# Connectors.net
KiCad netlist of a schematic drawn in Altium Designer
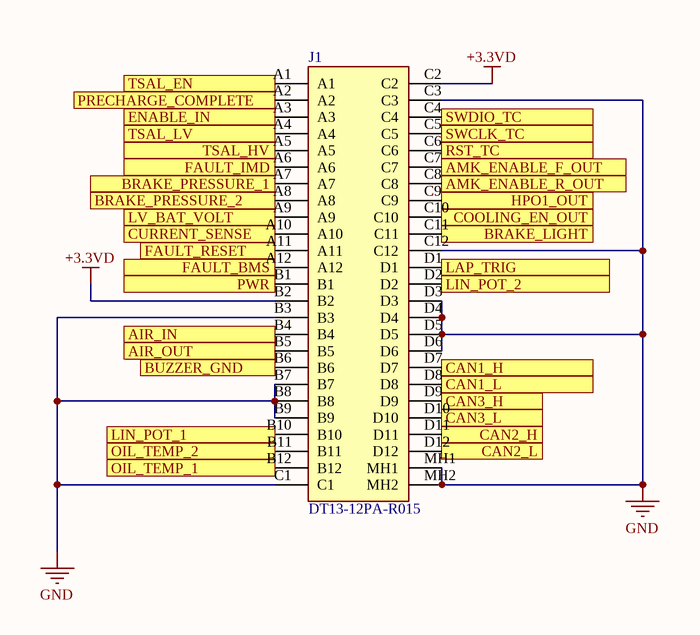
[diagram p0: Connectors.SchDoc]

(export (version "E")
  (design (tool "Eeschema 10.0.6"))
  (components
    (comp (ref "J1")
      (value "DT13-12PA-R015")
      (footprint "DT1312PAR015")
      (description "Automotive Connectors EEC HEADER")
      (fields (field (name "MOUSER PART NUMBER") "571-DT13-12PA-R015"))
      (libsource (lib "Illini Formula Electric") (part "DT13-12PA-R015"))
    )
  )
  (nets
    (net (code "1") (name "+3.3VD") (class "Default")
      (node (ref "J1") (pin "B2") (pinfunction "B2_B2") (pintype "passive"))
      (node (ref "J1") (pin "C2") (pinfunction "C2_C2") (pintype "passive"))
    )
    (net (code "2") (name "/AIR_IN") (class "Default")
      (node (ref "J1") (pin "B4") (pinfunction "B4_B4") (pintype "passive"))
    )
    (net (code "3") (name "/AIR_OUT") (class "Default")
      (node (ref "J1") (pin "B5") (pinfunction "B5_B5") (pintype "passive"))
    )
    (net (code "4") (name "/AMK_ENABLE_F_OUT") (class "Default")
      (node (ref "J1") (pin "C7") (pinfunction "C7_C7") (pintype "passive"))
    )
    (net (code "5") (name "/AMK_ENABLE_R_OUT") (class "Default")
      (node (ref "J1") (pin "C8") (pinfunction "C8_C8") (pintype "passive"))
    )
    (net (code "6") (name "/BRAKE_LIGHT") (class "Default")
      (node (ref "J1") (pin "C11") (pinfunction "C11_C11") (pintype "passive"))
    )
    (net (code "7") (name "/BRAKE_PRESSURE_1") (class "Default")
      (node (ref "J1") (pin "A7") (pinfunction "A7_A7") (pintype "passive"))
    )
    (net (code "8") (name "/BRAKE_PRESSURE_2") (class "Default")
      (node (ref "J1") (pin "A8") (pinfunction "A8_A8") (pintype "passive"))
    )
    (net (code "9") (name "/BUZZER_GND") (class "Default")
      (node (ref "J1") (pin "B6") (pinfunction "B6_B6") (pintype "passive"))
    )
    (net (code "10") (name "/CAN1_H") (class "Default")
      (node (ref "J1") (pin "D7") (pinfunction "D7_D7") (pintype "passive"))
    )
    (net (code "11") (name "/CAN1_L") (class "Default")
      (node (ref "J1") (pin "D8") (pinfunction "D8_D8") (pintype "passive"))
    )
    (net (code "12") (name "/CAN2_H") (class "Default")
      (node (ref "J1") (pin "D11") (pinfunction "D11_D11") (pintype "passive"))
    )
    (net (code "13") (name "/CAN2_L") (class "Default")
      (node (ref "J1") (pin "D12") (pinfunction "D12_D12") (pintype "passive"))
    )
    (net (code "14") (name "/CAN3_H") (class "Default")
      (node (ref "J1") (pin "D9") (pinfunction "D9_D9") (pintype "passive"))
    )
    (net (code "15") (name "/CAN3_L") (class "Default")
      (node (ref "J1") (pin "D10") (pinfunction "D10_D10") (pintype "passive"))
    )
    (net (code "16") (name "/COOLING_EN_OUT") (class "Default")
      (node (ref "J1") (pin "C10") (pinfunction "C10_C10") (pintype "passive"))
    )
    (net (code "17") (name "/CURRENT_SENSE") (class "Default")
      (node (ref "J1") (pin "A10") (pinfunction "A10_A10") (pintype "passive"))
    )
    (net (code "18") (name "/ENABLE_IN") (class "Default")
      (node (ref "J1") (pin "A3") (pinfunction "A3_A3") (pintype "passive"))
    )
    (net (code "19") (name "/FAULT_BMS") (class "Default")
      (node (ref "J1") (pin "A12") (pinfunction "A12_A12") (pintype "passive"))
    )
    (net (code "20") (name "/FAULT_IMD") (class "Default")
      (node (ref "J1") (pin "A6") (pinfunction "A6_A6") (pintype "passive"))
    )
    (net (code "21") (name "/FAULT_RESET") (class "Default")
      (node (ref "J1") (pin "A11") (pinfunction "A11_A11") (pintype "passive"))
    )
    (net (code "22") (name "/HPO1_OUT") (class "Default")
      (node (ref "J1") (pin "C9") (pinfunction "C9_C9") (pintype "passive"))
    )
    (net (code "23") (name "/LAP_TRIG") (class "Default")
      (node (ref "J1") (pin "D1") (pinfunction "D1_D1") (pintype "passive"))
    )
    (net (code "24") (name "/LIN_POT_1") (class "Default")
      (node (ref "J1") (pin "B10") (pinfunction "B10_B10") (pintype "passive"))
    )
    (net (code "25") (name "/LIN_POT_2") (class "Default")
      (node (ref "J1") (pin "D2") (pinfunction "D2_D2") (pintype "passive"))
    )
    (net (code "26") (name "/LV_BAT_VOLT") (class "Default")
      (node (ref "J1") (pin "A9") (pinfunction "A9_A9") (pintype "passive"))
    )
    (net (code "27") (name "/OIL_TEMP_1") (class "Default")
      (node (ref "J1") (pin "B12") (pinfunction "B12_B12") (pintype "passive"))
    )
    (net (code "28") (name "/OIL_TEMP_2") (class "Default")
      (node (ref "J1") (pin "B11") (pinfunction "B11_B11") (pintype "passive"))
    )
    (net (code "29") (name "/PRECHARGE_COMPLETE") (class "Default")
      (node (ref "J1") (pin "A2") (pinfunction "A2_A2") (pintype "passive"))
    )
    (net (code "30") (name "/PWR") (class "Default")
      (node (ref "J1") (pin "B1") (pinfunction "B1_B1") (pintype "passive"))
    )
    (net (code "31") (name "/RST_TC") (class "Default")
      (node (ref "J1") (pin "C6") (pinfunction "C6_C6") (pintype "passive"))
    )
    (net (code "32") (name "/SWCLK_TC") (class "Default")
      (node (ref "J1") (pin "C5") (pinfunction "C5_C5") (pintype "passive"))
    )
    (net (code "33") (name "/SWDIO_TC") (class "Default")
      (node (ref "J1") (pin "C4") (pinfunction "C4_C4") (pintype "passive"))
    )
    (net (code "34") (name "/TSAL_EN") (class "Default")
      (node (ref "J1") (pin "A1") (pinfunction "A1_A1") (pintype "passive"))
    )
    (net (code "35") (name "/TSAL_HV") (class "Default")
      (node (ref "J1") (pin "A5") (pinfunction "A5_A5") (pintype "passive"))
    )
    (net (code "36") (name "/TSAL_LV") (class "Default")
      (node (ref "J1") (pin "A4") (pinfunction "A4_A4") (pintype "passive"))
    )
    (net (code "37") (name "GND") (class "Default")
      (node (ref "J1") (pin "B3") (pinfunction "B3_B3") (pintype "passive"))
      (node (ref "J1") (pin "B7") (pinfunction "B7_B7") (pintype "passive"))
      (node (ref "J1") (pin "B8") (pinfunction "B8_B8") (pintype "passive"))
      (node (ref "J1") (pin "B9") (pinfunction "B9_B9") (pintype "passive"))
      (node (ref "J1") (pin "C1") (pinfunction "C1_C1") (pintype "passive"))
      (node (ref "J1") (pin "C12") (pinfunction "C12_C12") (pintype "passive"))
      (node (ref "J1") (pin "C3") (pinfunction "C3_C3") (pintype "passive"))
      (node (ref "J1") (pin "D3") (pinfunction "D3_D3") (pintype "passive"))
      (node (ref "J1") (pin "D4") (pinfunction "D4_D4") (pintype "passive"))
      (node (ref "J1") (pin "D5") (pinfunction "D5_D5") (pintype "passive"))
      (node (ref "J1") (pin "D6") (pinfunction "D6_D6") (pintype "passive"))
      (node (ref "J1") (pin "MH1") (pinfunction "MH1_MH1") (pintype "passive"))
      (node (ref "J1") (pin "MH2") (pinfunction "MH2_MH2") (pintype "passive"))
    )
  )
)
